# eDP.net
KiCad netlist of a schematic drawn in Altium Designer
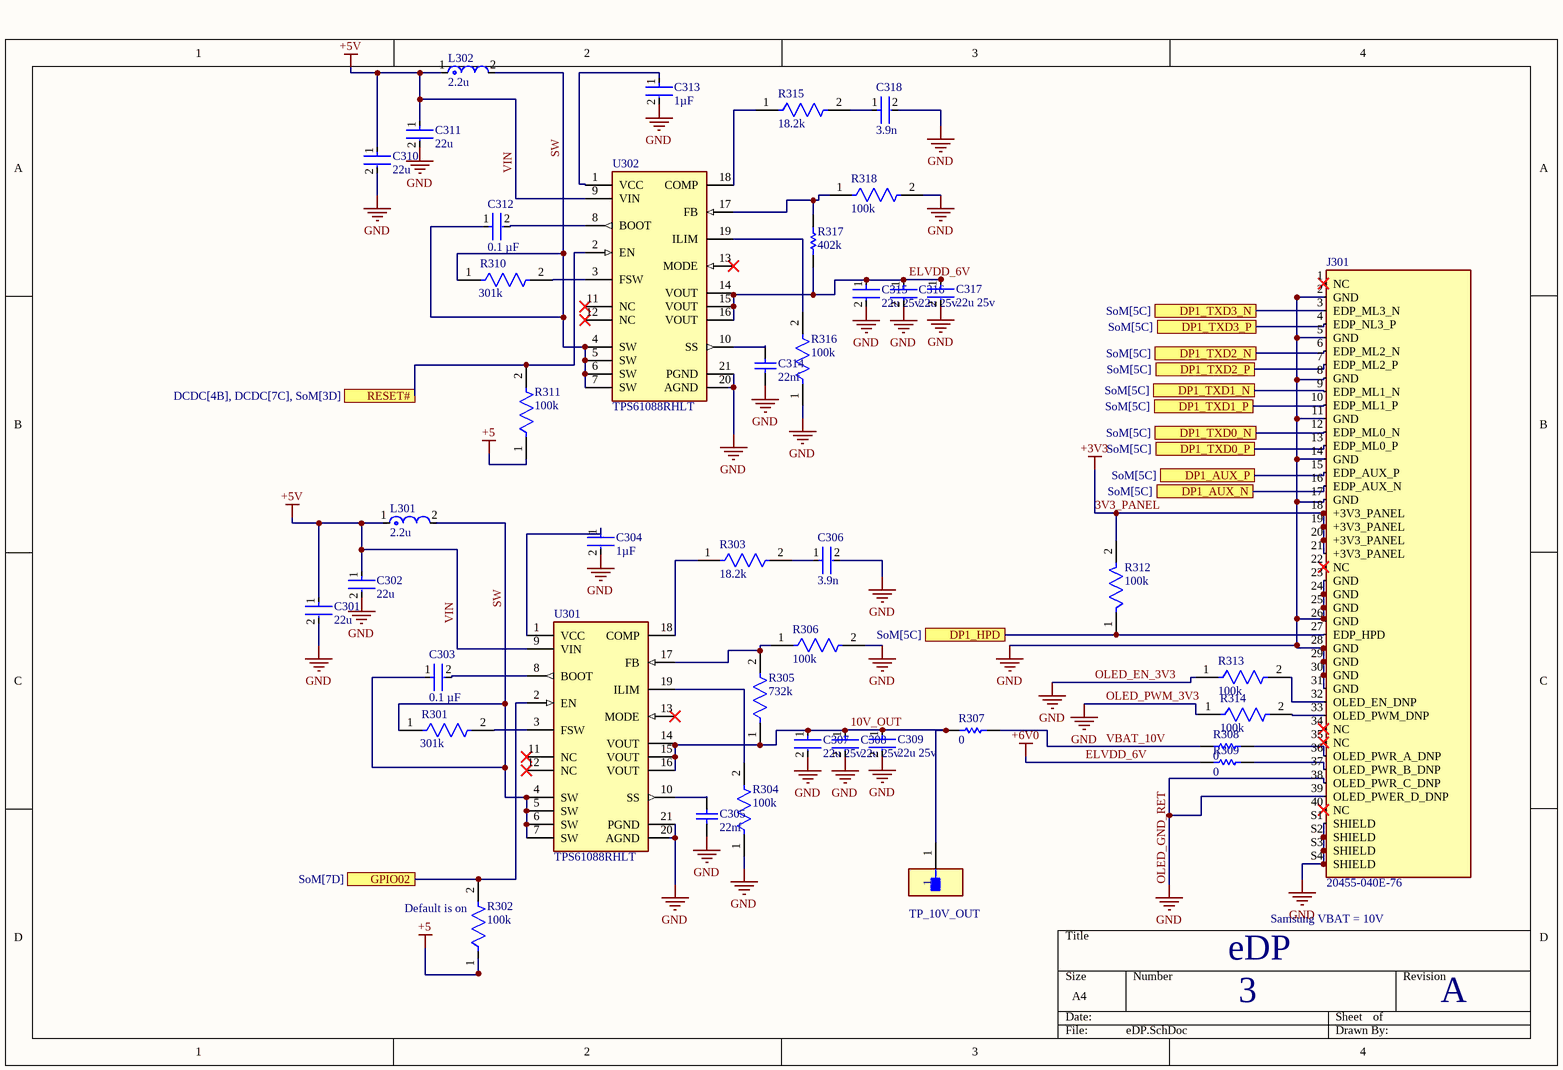
[diagram p0: eDP.SchDoc]

(export (version "E")
  (design (tool "Eeschema 10.0.6"))
  (components
    (comp (ref "C301")
      (value "22u")
      (footprint "FP-CL10-IPC_B")
      (description "Cap Ceramic 22uF 16V X5R ±20% Pad SMD 0603 +85°C T/R")
      (fields (field (name "TOLERANCE") "20%"))
      (libsource (lib "Altium Content Vault") (part "b4654b650e69147ec39a6b967a45e02"))
    )
    (comp (ref "C302")
      (value "22u")
      (footprint "FP-CL10-IPC_B")
      (description "Cap Ceramic 22uF 16V X5R ±20% Pad SMD 0603 +85°C T/R")
      (fields (field (name "TOLERANCE") "20%"))
      (libsource (lib "Altium Content Vault") (part "b4654b650e69147ec39a6b967a45e02"))
    )
    (comp (ref "C303")
      (value "0.1 µF")
      (footprint "FP-GRM155-0_05-IPC_B")
      (description "Chip Multilayer Ceramic Capacitors for General Purpose, 0402, 0.10uF, X7R, 15%, 10%, 50V")
      (fields (field (name "TOLERANCE") "10%"))
      (libsource (lib "Altium Content Vault") (part "02cd4be3c70576c341d710602a673aa"))
    )
    (comp (ref "C304")
      (value "1µF")
      (footprint "FP-GRM15-0_1-MFG")
      (description "CAP CER 1UF 10V X5R 0402")
      (fields
        (field (name "OCTOPART") "https://octopart.com/grm155r61a105ke15d-murata-197442")
        (field (name "MANUFACTURER PART NUMBER") "GRM155R61A105KE15D")
      )
      (libsource (lib "Altium Content Vault") (part "02cd4be3c70576c341d710602a673aa"))
    )
    (comp (ref "C305")
      (value "22nf")
      (footprint "CAPC1608X90X35ML10T15")
      (fields (field (name "MANUFACTURER") "Murata") (field (name "PART NUMBER") "GRM188R71H223KA01D"))
      (libsource (lib "Altium Content Vault") (part "CAP"))
    )
    (comp (ref "C306")
      (value "3.9n")
      (footprint "FP-GRM188-0_1-e0_2_0_5-IPC_B")
      (description "Chip Multilayer Ceramic Capacitors for General Purpose, 0603, 3900pF, C0G, 30ppm/°C, 5%, 50V")
      (fields (field (name "VOLTAGE") "50V") (field (name "TOLERANCE") "5%"))
      (libsource (lib "Altium Content Vault") (part "11868f565c42a9108669ba33697ecf6"))
    )
    (comp (ref "C307")
      (value "22u 25v")
      (footprint "FP-GRM21B-0_2-e0_2_0_7-IPC_B")
      (description "Chip Multilayer Ceramic Capacitors for General Purpose, 0805, 22uF, X5R, 15%, 20%, 25V")
      (fields (field (name "TOLERANCE") "20%") (field (name "VOLTAGE") "25V"))
      (libsource (lib "Altium Content Vault") (part "b4654b650e69147ec39a6b967a45e02"))
    )
    (comp (ref "C308")
      (value "22u 25v")
      (footprint "FP-GRM21B-0_2-e0_2_0_7-IPC_B")
      (description "Chip Multilayer Ceramic Capacitors for General Purpose, 0805, 22uF, X5R, 15%, 20%, 25V")
      (fields (field (name "TOLERANCE") "20%") (field (name "VOLTAGE") "25V"))
      (libsource (lib "Altium Content Vault") (part "b4654b650e69147ec39a6b967a45e02"))
    )
    (comp (ref "C309")
      (value "22u 25v")
      (footprint "FP-GRM21B-0_2-e0_2_0_7-IPC_B")
      (description "Chip Multilayer Ceramic Capacitors for General Purpose, 0805, 22uF, X5R, 15%, 20%, 25V")
      (fields (field (name "TOLERANCE") "20%") (field (name "VOLTAGE") "25V"))
      (libsource (lib "Altium Content Vault") (part "b4654b650e69147ec39a6b967a45e02"))
    )
    (comp (ref "C310")
      (value "22u")
      (footprint "FP-CL10-IPC_B")
      (description "Cap Ceramic 22uF 16V X5R ±20% Pad SMD 0603 +85°C T/R")
      (fields (field (name "TOLERANCE") "20%"))
      (libsource (lib "Altium Content Vault") (part "b4654b650e69147ec39a6b967a45e02"))
    )
    (comp (ref "C311")
      (value "22u")
      (footprint "FP-CL10-IPC_B")
      (description "Cap Ceramic 22uF 16V X5R ±20% Pad SMD 0603 +85°C T/R")
      (fields (field (name "TOLERANCE") "20%"))
      (libsource (lib "Altium Content Vault") (part "b4654b650e69147ec39a6b967a45e02"))
    )
    (comp (ref "C312")
      (value "0.1 µF")
      (footprint "FP-GRM155-0_05-IPC_B")
      (description "Chip Multilayer Ceramic Capacitors for General Purpose, 0402, 0.10uF, X7R, 15%, 10%, 50V")
      (fields (field (name "TOLERANCE") "10%"))
      (libsource (lib "Altium Content Vault") (part "02cd4be3c70576c341d710602a673aa"))
    )
    (comp (ref "C313")
      (value "1µF")
      (footprint "FP-GRM15-0_1-MFG")
      (description "CAP CER 1UF 10V X5R 0402")
      (fields
        (field (name "OCTOPART") "https://octopart.com/grm155r61a105ke15d-murata-197442")
        (field (name "MANUFACTURER PART NUMBER") "GRM155R61A105KE15D")
      )
      (libsource (lib "Altium Content Vault") (part "02cd4be3c70576c341d710602a673aa"))
    )
    (comp (ref "C314")
      (value "22nf")
      (footprint "CAPC1608X90X35ML10T15")
      (fields (field (name "MANUFACTURER") "Murata") (field (name "PART NUMBER") "GRM188R71H223KA01D"))
      (libsource (lib "Altium Content Vault") (part "CAP"))
    )
    (comp (ref "C315")
      (value "22u 25v")
      (footprint "FP-GRM21B-0_2-e0_2_0_7-IPC_B")
      (description "Chip Multilayer Ceramic Capacitors for General Purpose, 0805, 22uF, X5R, 15%, 20%, 25V")
      (fields (field (name "TOLERANCE") "20%") (field (name "VOLTAGE") "25V"))
      (libsource (lib "Altium Content Vault") (part "b4654b650e69147ec39a6b967a45e02"))
    )
    (comp (ref "C316")
      (value "22u 25v")
      (footprint "FP-GRM21B-0_2-e0_2_0_7-IPC_B")
      (description "Chip Multilayer Ceramic Capacitors for General Purpose, 0805, 22uF, X5R, 15%, 20%, 25V")
      (fields (field (name "TOLERANCE") "20%") (field (name "VOLTAGE") "25V"))
      (libsource (lib "Altium Content Vault") (part "b4654b650e69147ec39a6b967a45e02"))
    )
    (comp (ref "C317")
      (value "22u 25v")
      (footprint "FP-GRM21B-0_2-e0_2_0_7-IPC_B")
      (description "Chip Multilayer Ceramic Capacitors for General Purpose, 0805, 22uF, X5R, 15%, 20%, 25V")
      (fields (field (name "TOLERANCE") "20%") (field (name "VOLTAGE") "25V"))
      (libsource (lib "Altium Content Vault") (part "b4654b650e69147ec39a6b967a45e02"))
    )
    (comp (ref "C318")
      (value "3.9n")
      (footprint "FP-GRM188-0_1-e0_2_0_5-IPC_B")
      (description "Chip Multilayer Ceramic Capacitors for General Purpose, 0603, 3900pF, C0G, 30ppm/°C, 5%, 50V")
      (fields (field (name "VOLTAGE") "50V") (field (name "TOLERANCE") "5%"))
      (libsource (lib "Altium Content Vault") (part "11868f565c42a9108669ba33697ecf6"))
    )
    (comp (ref "J300")
      (value "TP_10V_OUT")
      (footprint "FP-S2751-46R-MFG")
      (description "10V nominal")
      (libsource (lib "Altium Content Vault") (part "dd45045ce8184df9e99e12baf3f412c"))
    )
    (comp (ref "J301")
      (value "20455-040E-76")
      (footprint "IPEX_20455-040E-76")
      (description "Conn Wire to Board RCP 40 POS 0.5mm Solder RA Side Entry SMDCABLINE® T/R")
      (libsource (lib "Evan") (part "20455-040E-76"))
    )
    (comp (ref "L301")
      (value "2.2u")
      (footprint "FP-XAL5030-222MEC-MFG")
      (description "Fixed Inductors 2.2uH Shld 20% 9.2A 14.5mOhms AECQ2 SRF: 38MHz Test Freq: 1MHz")
      (fields (field (name "TOLERANCE") "20%"))
      (libsource (lib "Altium Content Vault") (part "4cc4b267dca4c8e51f7102f422741d8"))
    )
    (comp (ref "L302")
      (value "2.2u")
      (footprint "FP-XAL5030-222MEC-MFG")
      (description "Fixed Inductors 2.2uH Shld 20% 9.2A 14.5mOhms AECQ2 SRF: 38MHz Test Freq: 1MHz")
      (fields (field (name "TOLERANCE") "20%"))
      (libsource (lib "Altium Content Vault") (part "4cc4b267dca4c8e51f7102f422741d8"))
    )
    (comp (ref "R301")
      (value "301k")
      (footprint "FP-CRCW0603-e3-IPC_C")
      (description "RES Thick Film, 301kΩ, 1%, 0.1W, 100ppm/°C, 0603")
      (fields (field (name "TOLERANCE") "1%"))
      (libsource (lib "Altium Content Vault") (part "1029c3af85768c4190bb7ad29bc67b5"))
    )
    (comp (ref "R302")
      (value "100k")
      (footprint "FP-CRCW0603C-e3-MFG")
      (description "RES SMD 100K OHM 1% 1/10W 0603")
      (fields (field (name "TOLERANCE") "1%"))
      (libsource (lib "Altium Content Vault") (part "1029c3af85768c4190bb7ad29bc67b5"))
    )
    (comp (ref "R303")
      (value "18.2k")
      (footprint "FP-CRCW0603-e3-IPC_C")
      (description "RES Thick Film, 18.2kΩ, 1%, 0.1W, 100ppm/°C, 0603")
      (fields (field (name "TOLERANCE") "1%"))
      (libsource (lib "Altium Content Vault") (part "1029c3af85768c4190bb7ad29bc67b5"))
    )
    (comp (ref "R304")
      (value "100k")
      (footprint "FP-CRCW0603C-e3-MFG")
      (description "RES SMD 100K OHM 1% 1/10W 0603")
      (fields (field (name "TOLERANCE") "1%"))
      (libsource (lib "Altium Content Vault") (part "1029c3af85768c4190bb7ad29bc67b5"))
    )
    (comp (ref "R305")
      (value "732k")
      (footprint "FP-CRCW0603-e3-IPC_B")
      (description "RES Thick Film, 732kΩ, 1%, 0.1W, 100ppm/°C, 0603")
      (fields (field (name "TOLERANCE") "1%"))
      (libsource (lib "Altium Content Vault") (part "1029c3af85768c4190bb7ad29bc67b5"))
    )
    (comp (ref "R306")
      (value "100k")
      (footprint "FP-CRCW0603C-e3-MFG")
      (description "RES SMD 100K OHM 1% 1/10W 0603")
      (fields (field (name "TOLERANCE") "1%"))
      (libsource (lib "Altium Content Vault") (part "1029c3af85768c4190bb7ad29bc67b5"))
    )
    (comp (ref "R307")
      (value "0")
      (footprint "RESC1005X40X25NL05T10")
      (fields (field (name "MANUFACTURER") "Yageo / Phycomp") (field (name "PART NUMBER") "RC0402JR-070RL"))
      (libsource (lib "Altium Content Vault") (part "RES"))
    )
    (comp (ref "R308")
      (value "0")
      (footprint "RESC1005X40X25NL05T10")
      (fields (field (name "MANUFACTURER") "Yageo / Phycomp") (field (name "PART NUMBER") "RC0402JR-070RL"))
      (libsource (lib "Altium Content Vault") (part "RES"))
    )
    (comp (ref "R309")
      (value "0")
      (footprint "RESC1005X40X25NL05T10")
      (fields (field (name "MANUFACTURER") "Yageo / Phycomp") (field (name "PART NUMBER") "RC0402JR-070RL"))
      (libsource (lib "Altium Content Vault") (part "RES"))
    )
    (comp (ref "R310")
      (value "301k")
      (footprint "FP-CRCW0603-e3-IPC_C")
      (description "RES Thick Film, 301kΩ, 1%, 0.1W, 100ppm/°C, 0603")
      (fields (field (name "TOLERANCE") "1%"))
      (libsource (lib "Altium Content Vault") (part "1029c3af85768c4190bb7ad29bc67b5"))
    )
    (comp (ref "R311")
      (value "100k")
      (footprint "FP-CRCW0603C-e3-MFG")
      (description "RES SMD 100K OHM 1% 1/10W 0603")
      (fields (field (name "TOLERANCE") "1%"))
      (libsource (lib "Altium Content Vault") (part "1029c3af85768c4190bb7ad29bc67b5"))
    )
    (comp (ref "R312")
      (value "100k")
      (footprint "FP-RC0402-0_4-IPC_A")
      (description "RES 100K OHM 5% 1/16W 0402")
      (fields (field (name "TOLERANCE") "5%"))
      (libsource (lib "Altium Content Vault") (part "1029c3af85768c4190bb7ad29bc67b5"))
    )
    (comp (ref "R313")
      (value "100k")
      (footprint "FP-CRCW0603C-e3-MFG")
      (description "RES SMD 100K OHM 1% 1/10W 0603")
      (fields (field (name "TOLERANCE") "1%"))
      (libsource (lib "Altium Content Vault") (part "1029c3af85768c4190bb7ad29bc67b5"))
    )
    (comp (ref "R314")
      (value "100k")
      (footprint "FP-CRCW0603C-e3-MFG")
      (description "RES SMD 100K OHM 1% 1/10W 0603")
      (fields (field (name "TOLERANCE") "1%"))
      (libsource (lib "Altium Content Vault") (part "1029c3af85768c4190bb7ad29bc67b5"))
    )
    (comp (ref "R315")
      (value "18.2k")
      (footprint "FP-CRCW0603-e3-IPC_C")
      (description "RES Thick Film, 18.2kΩ, 1%, 0.1W, 100ppm/°C, 0603")
      (fields (field (name "TOLERANCE") "1%"))
      (libsource (lib "Altium Content Vault") (part "1029c3af85768c4190bb7ad29bc67b5"))
    )
    (comp (ref "R316")
      (value "100k")
      (footprint "FP-CRCW0603C-e3-MFG")
      (description "RES SMD 100K OHM 1% 1/10W 0603")
      (fields (field (name "TOLERANCE") "1%"))
      (libsource (lib "Altium Content Vault") (part "1029c3af85768c4190bb7ad29bc67b5"))
    )
    (comp (ref "R317")
      (value "402k")
      (footprint "RESC1609X50X30ML10T20")
      (fields (field (name "MANUFACTURER") "Vishay Dale") (field (name "PART NUMBER") "CRCW0603402KFKEA"))
      (libsource (lib "Altium Content Vault") (part "RES"))
    )
    (comp (ref "R318")
      (value "100k")
      (footprint "FP-CRCW0603C-e3-MFG")
      (description "RES SMD 100K OHM 1% 1/10W 0603")
      (fields (field (name "TOLERANCE") "1%"))
      (libsource (lib "Altium Content Vault") (part "1029c3af85768c4190bb7ad29bc67b5"))
    )
    (comp (ref "U301")
      (value "TPS61088RHLT")
      (footprint "FP-RHL0020A-MFG")
      (description "IC REG BOOST ADJ 10A 20VQFN")
      (fields
        (field (name "OCTOPART") "https://octopart.com/tps61088rhlt-texas+instruments-57155059")
        (field (name "MANUFACTURER") "Texas Instruments")
      )
      (libsource (lib "Altium Content Vault") (part "866d791168d43c93e8e886550da2fd8"))
    )
    (comp (ref "U302")
      (value "TPS61088RHLT")
      (footprint "FP-RHL0020A-MFG")
      (description "IC REG BOOST ADJ 10A 20VQFN")
      (fields
        (field (name "OCTOPART") "https://octopart.com/tps61088rhlt-texas+instruments-57155059")
        (field (name "MANUFACTURER") "Texas Instruments")
      )
      (libsource (lib "Altium Content Vault") (part "866d791168d43c93e8e886550da2fd8"))
    )
  )
  (nets
    (net (code "1") (name "+3V3") (class "Default")
      (node (ref "J301") (pin "18") (pinfunction "+3V3_PANEL_18") (pintype "passive"))
      (node (ref "J301") (pin "19") (pinfunction "+3V3_PANEL_19") (pintype "passive"))
      (node (ref "J301") (pin "20") (pinfunction "+3V3_PANEL_20") (pintype "passive"))
      (node (ref "J301") (pin "21") (pinfunction "+3V3_PANEL_21") (pintype "passive"))
      (node (ref "R312") (pin "2") (pinfunction "2_2") (pintype "passive"))
    )
    (net (code "2") (name "+5") (class "Default")
      (node (ref "R302") (pin "1") (pinfunction "1_1") (pintype "passive"))
      (node (ref "R311") (pin "1") (pinfunction "1_1") (pintype "passive"))
    )
    (net (code "3") (name "+5V") (class "Default")
      (node (ref "C301") (pin "1") (pinfunction "1_1") (pintype "passive"))
      (node (ref "C302") (pin "1") (pinfunction "1_1") (pintype "passive"))
      (node (ref "C310") (pin "1") (pinfunction "1_1") (pintype "passive"))
      (node (ref "C311") (pin "1") (pinfunction "1_1") (pintype "passive"))
      (node (ref "L301") (pin "1") (pinfunction "1_1") (pintype "passive"))
      (node (ref "L302") (pin "1") (pinfunction "1_1") (pintype "passive"))
      (node (ref "U301") (pin "9") (pinfunction "VIN_9") (pintype "power_in"))
      (node (ref "U302") (pin "9") (pinfunction "VIN_9") (pintype "power_in"))
    )
    (net (code "4") (name "+6V0") (class "Default")
      (node (ref "C315") (pin "1") (pinfunction "1_1") (pintype "passive"))
      (node (ref "C316") (pin "1") (pinfunction "1_1") (pintype "passive"))
      (node (ref "C317") (pin "1") (pinfunction "1_1") (pintype "passive"))
      (node (ref "R309") (pin "1") (pinfunction "1_1") (pintype "passive"))
      (node (ref "R317") (pin "1") (pinfunction "1_1") (pintype "passive"))
      (node (ref "U302") (pin "14") (pinfunction "VOUT_14") (pintype "power_in"))
      (node (ref "U302") (pin "15") (pinfunction "VOUT_15") (pintype "power_in"))
      (node (ref "U302") (pin "16") (pinfunction "VOUT_16") (pintype "power_in"))
    )
    (net (code "5") (name "/10V_OUT") (class "Default")
      (node (ref "C307") (pin "1") (pinfunction "1_1") (pintype "passive"))
      (node (ref "C308") (pin "1") (pinfunction "1_1") (pintype "passive"))
      (node (ref "C309") (pin "1") (pinfunction "1_1") (pintype "passive"))
      (node (ref "J300") (pin "1") (pinfunction "1_1") (pintype "passive"))
      (node (ref "R305") (pin "1") (pinfunction "1_1") (pintype "passive"))
      (node (ref "R307") (pin "1") (pinfunction "1_1") (pintype "passive"))
      (node (ref "U301") (pin "14") (pinfunction "VOUT_14") (pintype "power_in"))
      (node (ref "U301") (pin "15") (pinfunction "VOUT_15") (pintype "power_in"))
      (node (ref "U301") (pin "16") (pinfunction "VOUT_16") (pintype "power_in"))
    )
    (net (code "6") (name "/DP1_AUX_N") (class "Default")
      (node (ref "J301") (pin "16") (pinfunction "EDP_AUX_N_16") (pintype "passive"))
    )
    (net (code "7") (name "/DP1_AUX_P") (class "Default")
      (node (ref "J301") (pin "15") (pinfunction "EDP_AUX_P_15") (pintype "passive"))
    )
    (net (code "8") (name "/DP1_HPD") (class "Default")
      (node (ref "J301") (pin "27") (pinfunction "EDP_HPD_27") (pintype "passive"))
      (node (ref "R312") (pin "1") (pinfunction "1_1") (pintype "passive"))
    )
    (net (code "9") (name "/DP1_TXD0_N") (class "Default")
      (node (ref "J301") (pin "12") (pinfunction "EDP_ML0_N_12") (pintype "passive"))
    )
    (net (code "10") (name "/DP1_TXD0_P") (class "Default")
      (node (ref "J301") (pin "13") (pinfunction "EDP_ML0_P_13") (pintype "passive"))
    )
    (net (code "11") (name "/DP1_TXD1_N") (class "Default")
      (node (ref "J301") (pin "9") (pinfunction "EDP_ML1_N_9") (pintype "passive"))
    )
    (net (code "12") (name "/DP1_TXD1_P") (class "Default")
      (node (ref "J301") (pin "10") (pinfunction "EDP_ML1_P_10") (pintype "passive"))
    )
    (net (code "13") (name "/DP1_TXD2_N") (class "Default")
      (node (ref "J301") (pin "6") (pinfunction "EDP_ML2_N_6") (pintype "passive"))
    )
    (net (code "14") (name "/DP1_TXD2_P") (class "Default")
      (node (ref "J301") (pin "7") (pinfunction "EDP_ML2_P_7") (pintype "passive"))
    )
    (net (code "15") (name "/DP1_TXD3_N") (class "Default")
      (node (ref "J301") (pin "3") (pinfunction "EDP_ML3_N_3") (pintype "passive"))
    )
    (net (code "16") (name "/DP1_TXD3_P") (class "Default")
      (node (ref "J301") (pin "4") (pinfunction "EDP_NL3_P_4") (pintype "passive"))
    )
    (net (code "17") (name "/GPIO02") (class "Default")
      (node (ref "R302") (pin "2") (pinfunction "2_2") (pintype "passive"))
      (node (ref "U301") (pin "2") (pinfunction "EN_2") (pintype "input"))
    )
    (net (code "18") (name "/RESET#") (class "Default")
      (node (ref "R311") (pin "2") (pinfunction "2_2") (pintype "passive"))
      (node (ref "U302") (pin "2") (pinfunction "EN_2") (pintype "input"))
    )
    (net (code "19") (name "/SW") (class "Default")
      (node (ref "C303") (pin "1") (pinfunction "1_1") (pintype "passive"))
      (node (ref "C312") (pin "1") (pinfunction "1_1") (pintype "passive"))
      (node (ref "L301") (pin "2") (pinfunction "2_2") (pintype "passive"))
      (node (ref "L302") (pin "2") (pinfunction "2_2") (pintype "passive"))
      (node (ref "R301") (pin "1") (pinfunction "1_1") (pintype "passive"))
      (node (ref "R310") (pin "1") (pinfunction "1_1") (pintype "passive"))
      (node (ref "U301") (pin "4") (pinfunction "SW_4") (pintype "power_in"))
      (node (ref "U301") (pin "5") (pinfunction "SW_5") (pintype "power_in"))
      (node (ref "U301") (pin "6") (pinfunction "SW_6") (pintype "power_in"))
      (node (ref "U301") (pin "7") (pinfunction "SW_7") (pintype "power_in"))
      (node (ref "U302") (pin "4") (pinfunction "SW_4") (pintype "power_in"))
      (node (ref "U302") (pin "5") (pinfunction "SW_5") (pintype "power_in"))
      (node (ref "U302") (pin "6") (pinfunction "SW_6") (pintype "power_in"))
      (node (ref "U302") (pin "7") (pinfunction "SW_7") (pintype "power_in"))
    )
    (net (code "20") (name "/VBAT_10V") (class "Default")
      (node (ref "R307") (pin "2") (pinfunction "2_2") (pintype "passive"))
      (node (ref "R308") (pin "1") (pinfunction "1_1") (pintype "passive"))
    )
    (net (code "21") (name "GND") (class "Default")
      (node (ref "C301") (pin "2") (pinfunction "2_2") (pintype "passive"))
      (node (ref "C302") (pin "2") (pinfunction "2_2") (pintype "passive"))
      (node (ref "C304") (pin "2") (pinfunction "2_2") (pintype "passive"))
      (node (ref "C305") (pin "1") (pinfunction "1_1") (pintype "passive"))
      (node (ref "C306") (pin "2") (pinfunction "2_2") (pintype "passive"))
      (node (ref "C307") (pin "2") (pinfunction "2_2") (pintype "passive"))
      (node (ref "C308") (pin "2") (pinfunction "2_2") (pintype "passive"))
      (node (ref "C309") (pin "2") (pinfunction "2_2") (pintype "passive"))
      (node (ref "C310") (pin "2") (pinfunction "2_2") (pintype "passive"))
      (node (ref "C311") (pin "2") (pinfunction "2_2") (pintype "passive"))
      (node (ref "C313") (pin "2") (pinfunction "2_2") (pintype "passive"))
      (node (ref "C314") (pin "1") (pinfunction "1_1") (pintype "passive"))
      (node (ref "C315") (pin "2") (pinfunction "2_2") (pintype "passive"))
      (node (ref "C316") (pin "2") (pinfunction "2_2") (pintype "passive"))
      (node (ref "C317") (pin "2") (pinfunction "2_2") (pintype "passive"))
      (node (ref "C318") (pin "2") (pinfunction "2_2") (pintype "passive"))
      (node (ref "J301") (pin "11") (pinfunction "GND_11") (pintype "passive"))
      (node (ref "J301") (pin "14") (pinfunction "GND_14") (pintype "passive"))
      (node (ref "J301") (pin "17") (pinfunction "GND_17") (pintype "passive"))
      (node (ref "J301") (pin "2") (pinfunction "GND_2") (pintype "passive"))
      (node (ref "J301") (pin "23") (pinfunction "GND_23") (pintype "passive"))
      (node (ref "J301") (pin "24") (pinfunction "GND_24") (pintype "passive"))
      (node (ref "J301") (pin "25") (pinfunction "GND_25") (pintype "passive"))
      (node (ref "J301") (pin "26") (pinfunction "GND_26") (pintype "passive"))
      (node (ref "J301") (pin "28") (pinfunction "GND_28") (pintype "passive"))
      (node (ref "J301") (pin "29") (pinfunction "GND_29") (pintype "passive"))
      (node (ref "J301") (pin "30") (pinfunction "GND_30") (pintype "passive"))
      (node (ref "J301") (pin "31") (pinfunction "GND_31") (pintype "passive"))
      (node (ref "J301") (pin "38") (pinfunction "OLED_PWR_C_DNP_38") (pintype "passive"))
      (node (ref "J301") (pin "39") (pinfunction "OLED_PWER_D_DNP_39") (pintype "passive"))
      (node (ref "J301") (pin "5") (pinfunction "GND_5") (pintype "passive"))
      (node (ref "J301") (pin "8") (pinfunction "GND_8") (pintype "passive"))
      (node (ref "J301") (pin "S1") (pinfunction "SHIELD_S1") (pintype "passive"))
      (node (ref "J301") (pin "S2") (pinfunction "SHIELD_S2") (pintype "passive"))
      (node (ref "J301") (pin "S3") (pinfunction "SHIELD_S3") (pintype "passive"))
      (node (ref "J301") (pin "S4") (pinfunction "SHIELD_S4") (pintype "passive"))
      (node (ref "R304") (pin "1") (pinfunction "1_1") (pintype "passive"))
      (node (ref "R306") (pin "2") (pinfunction "2_2") (pintype "passive"))
      (node (ref "R313") (pin "1") (pinfunction "1_1") (pintype "passive"))
      (node (ref "R314") (pin "1") (pinfunction "1_1") (pintype "passive"))
      (node (ref "R316") (pin "1") (pinfunction "1_1") (pintype "passive"))
      (node (ref "R318") (pin "2") (pinfunction "2_2") (pintype "passive"))
      (node (ref "U301") (pin "20") (pinfunction "AGND_20") (pintype "power_in"))
      (node (ref "U301") (pin "21") (pinfunction "PGND_21") (pintype "power_in"))
      (node (ref "U302") (pin "20") (pinfunction "AGND_20") (pintype "power_in"))
      (node (ref "U302") (pin "21") (pinfunction "PGND_21") (pintype "power_in"))
    )
    (net (code "22") (name "Net-(C306-Pad1)") (class "Default")
      (node (ref "C306") (pin "1") (pinfunction "1_1") (pintype "passive"))
      (node (ref "R303") (pin "2") (pinfunction "2_2") (pintype "passive"))
    )
    (net (code "23") (name "Net-(C318-Pad1)") (class "Default")
      (node (ref "C318") (pin "1") (pinfunction "1_1") (pintype "passive"))
      (node (ref "R315") (pin "2") (pinfunction "2_2") (pintype "passive"))
    )
    (net (code "24") (name "Net-(J301-OLED_EN_DNP)") (class "Default")
      (node (ref "J301") (pin "32") (pinfunction "OLED_EN_DNP_32") (pintype "passive"))
      (node (ref "R313") (pin "2") (pinfunction "2_2") (pintype "passive"))
    )
    (net (code "25") (name "Net-(J301-OLED_PWM_DNP)") (class "Default")
      (node (ref "J301") (pin "33") (pinfunction "OLED_PWM_DNP_33") (pintype "passive"))
      (node (ref "R314") (pin "2") (pinfunction "2_2") (pintype "passive"))
    )
    (net (code "26") (name "Net-(J301-OLED_PWR_A_DNP)") (class "Default")
      (node (ref "J301") (pin "36") (pinfunction "OLED_PWR_A_DNP_36") (pintype "passive"))
      (node (ref "R308") (pin "2") (pinfunction "2_2") (pintype "passive"))
    )
    (net (code "27") (name "Net-(J301-OLED_PWR_B_DNP)") (class "Default")
      (node (ref "J301") (pin "37") (pinfunction "OLED_PWR_B_DNP_37") (pintype "passive"))
      (node (ref "R309") (pin "2") (pinfunction "2_2") (pintype "passive"))
    )
    (net (code "28") (name "Net-(U301-BOOT)") (class "Default")
      (node (ref "C303") (pin "2") (pinfunction "2_2") (pintype "passive"))
      (node (ref "U301") (pin "8") (pinfunction "BOOT_8") (pintype "output"))
    )
    (net (code "29") (name "Net-(U301-COMP)") (class "Default")
      (node (ref "R303") (pin "1") (pinfunction "1_1") (pintype "passive"))
      (node (ref "U301") (pin "18") (pinfunction "COMP_18") (pintype "passive"))
    )
    (net (code "30") (name "Net-(U301-FB)") (class "Default")
      (node (ref "R305") (pin "2") (pinfunction "2_2") (pintype "passive"))
      (node (ref "R306") (pin "1") (pinfunction "1_1") (pintype "passive"))
      (node (ref "U301") (pin "17") (pinfunction "FB_17") (pintype "input"))
    )
    (net (code "31") (name "Net-(U301-FSW)") (class "Default")
      (node (ref "R301") (pin "2") (pinfunction "2_2") (pintype "passive"))
      (node (ref "U301") (pin "3") (pinfunction "FSW_3") (pintype "passive"))
    )
    (net (code "32") (name "Net-(U301-ILIM)") (class "Default")
      (node (ref "R304") (pin "2") (pinfunction "2_2") (pintype "passive"))
      (node (ref "U301") (pin "19") (pinfunction "ILIM_19") (pintype "passive"))
    )
    (net (code "33") (name "Net-(U301-SS)") (class "Default")
      (node (ref "C305") (pin "2") (pinfunction "2_2") (pintype "passive"))
      (node (ref "U301") (pin "10") (pinfunction "SS_10") (pintype "output"))
    )
    (net (code "34") (name "Net-(U301-VCC)") (class "Default")
      (node (ref "C304") (pin "1") (pinfunction "1_1") (pintype "passive"))
      (node (ref "U301") (pin "1") (pinfunction "VCC_1") (pintype "power_in"))
    )
    (net (code "35") (name "Net-(U302-BOOT)") (class "Default")
      (node (ref "C312") (pin "2") (pinfunction "2_2") (pintype "passive"))
      (node (ref "U302") (pin "8") (pinfunction "BOOT_8") (pintype "output"))
    )
    (net (code "36") (name "Net-(U302-COMP)") (class "Default")
      (node (ref "R315") (pin "1") (pinfunction "1_1") (pintype "passive"))
      (node (ref "U302") (pin "18") (pinfunction "COMP_18") (pintype "passive"))
    )
    (net (code "37") (name "Net-(U302-FB)") (class "Default")
      (node (ref "R317") (pin "2") (pinfunction "2_2") (pintype "passive"))
      (node (ref "R318") (pin "1") (pinfunction "1_1") (pintype "passive"))
      (node (ref "U302") (pin "17") (pinfunction "FB_17") (pintype "input"))
    )
    (net (code "38") (name "Net-(U302-FSW)") (class "Default")
      (node (ref "R310") (pin "2") (pinfunction "2_2") (pintype "passive"))
      (node (ref "U302") (pin "3") (pinfunction "FSW_3") (pintype "passive"))
    )
    (net (code "39") (name "Net-(U302-ILIM)") (class "Default")
      (node (ref "R316") (pin "2") (pinfunction "2_2") (pintype "passive"))
      (node (ref "U302") (pin "19") (pinfunction "ILIM_19") (pintype "passive"))
    )
    (net (code "40") (name "Net-(U302-SS)") (class "Default")
      (node (ref "C314") (pin "2") (pinfunction "2_2") (pintype "passive"))
      (node (ref "U302") (pin "10") (pinfunction "SS_10") (pintype "output"))
    )
    (net (code "41") (name "Net-(U302-VCC)") (class "Default")
      (node (ref "C313") (pin "1") (pinfunction "1_1") (pintype "passive"))
      (node (ref "U302") (pin "1") (pinfunction "VCC_1") (pintype "power_in"))
    )
    (net (code "42") (name "unconnected-(J301-NC-Pad1)") (class "Default")
      (node (ref "J301") (pin "1") (pinfunction "NC_1") (pintype "passive+no_connect"))
    )
    (net (code "43") (name "unconnected-(J301-NC-Pad22)") (class "Default")
      (node (ref "J301") (pin "22") (pinfunction "NC_22") (pintype "passive+no_connect"))
    )
    (net (code "44") (name "unconnected-(J301-NC-Pad34)") (class "Default")
      (node (ref "J301") (pin "34") (pinfunction "NC_34") (pintype "passive+no_connect"))
    )
    (net (code "45") (name "unconnected-(J301-NC-Pad35)") (class "Default")
      (node (ref "J301") (pin "35") (pinfunction "NC_35") (pintype "passive+no_connect"))
    )
    (net (code "46") (name "unconnected-(J301-NC-Pad40)") (class "Default")
      (node (ref "J301") (pin "40") (pinfunction "NC_40") (pintype "passive+no_connect"))
    )
    (net (code "47") (name "unconnected-(U301-MODE-Pad13)") (class "Default")
      (node (ref "U301") (pin "13") (pinfunction "MODE_13") (pintype "input+no_connect"))
    )
    (net (code "48") (name "unconnected-(U301-NC-Pad11)") (class "Default")
      (node (ref "U301") (pin "11") (pinfunction "NC_11") (pintype "passive+no_connect"))
    )
    (net (code "49") (name "unconnected-(U301-NC-Pad12)") (class "Default")
      (node (ref "U301") (pin "12") (pinfunction "NC_12") (pintype "passive+no_connect"))
    )
    (net (code "50") (name "unconnected-(U302-MODE-Pad13)") (class "Default")
      (node (ref "U302") (pin "13") (pinfunction "MODE_13") (pintype "input+no_connect"))
    )
    (net (code "51") (name "unconnected-(U302-NC-Pad11)") (class "Default")
      (node (ref "U302") (pin "11") (pinfunction "NC_11") (pintype "passive+no_connect"))
    )
    (net (code "52") (name "unconnected-(U302-NC-Pad12)") (class "Default")
      (node (ref "U302") (pin "12") (pinfunction "NC_12") (pintype "passive+no_connect"))
    )
  )
)
